# FSWSJE2IZ6BVKJ2.net
KiCad netlist of a schematic drawn in EAGLE
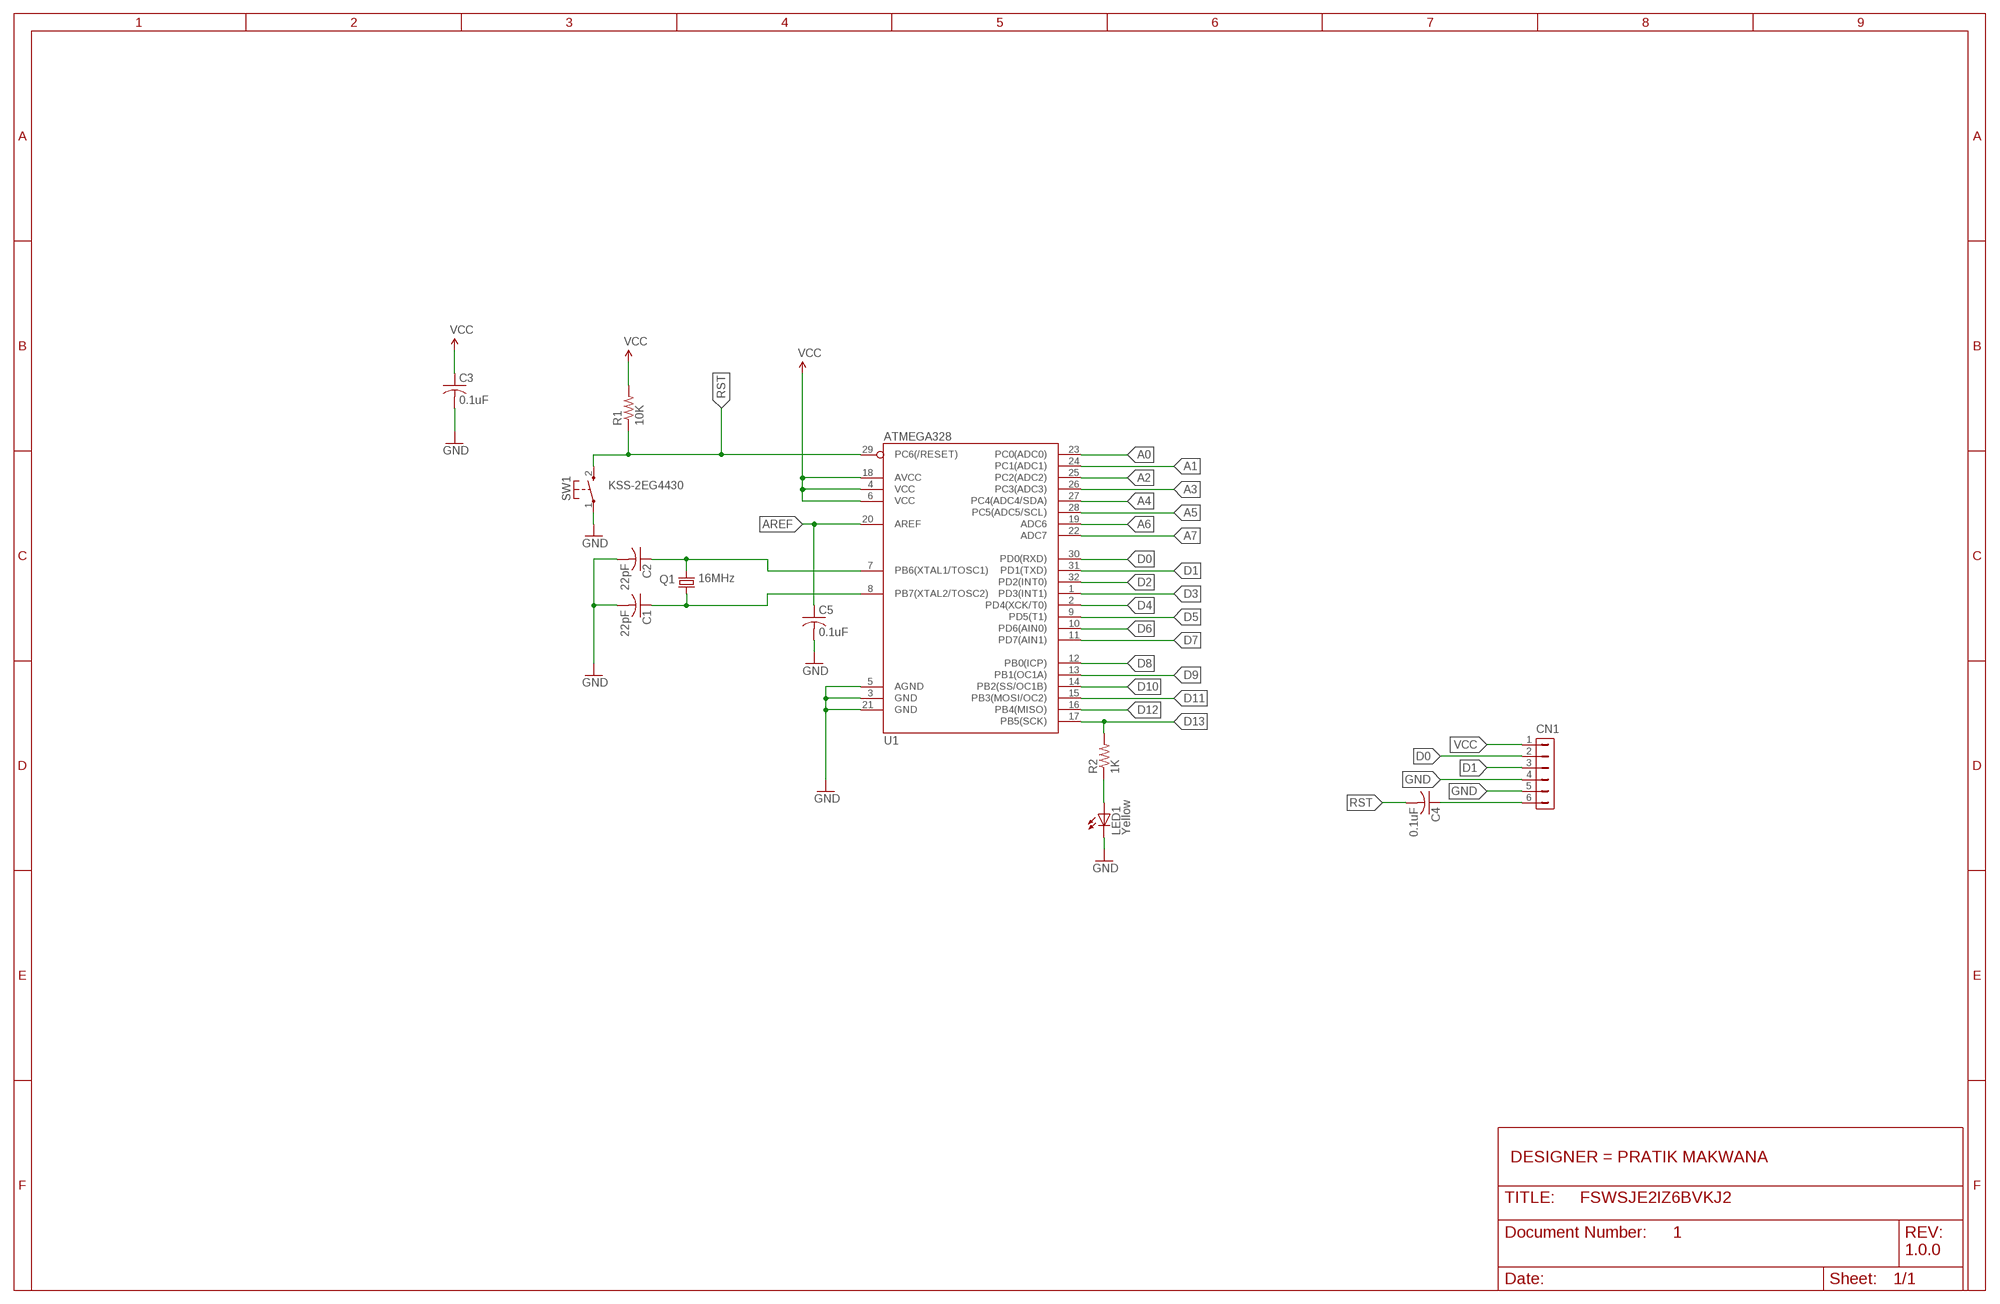
[diagram p0: schematic, sheet 1]

(export (version "E")
  (design (tool "Eeschema 10.0.6"))
  (components
    (comp (ref "C1")
      (value "22pF")
      (footprint "eagle-import:C1206")
      (libsource (lib "eagle-import") (part "C-USC1206"))
    )
    (comp (ref "C2")
      (value "22pF")
      (footprint "eagle-import:C1206")
      (libsource (lib "eagle-import") (part "C-USC1206"))
    )
    (comp (ref "C3")
      (value "0.1uF")
      (footprint "eagle-import:C0805")
      (libsource (lib "eagle-import") (part "C-USC0805"))
    )
    (comp (ref "C4")
      (value "0.1uF")
      (footprint "eagle-import:C0805")
      (libsource (lib "eagle-import") (part "C-USC0805"))
    )
    (comp (ref "C5")
      (value "0.1uF")
      (footprint "eagle-import:C0805")
      (libsource (lib "eagle-import") (part "C-USC0805"))
    )
    (comp (ref "CN1")
      (value "HDR-1X6-SIP-100")
      (footprint "eagle-import:SIP-100-6V")
      (libsource (lib "eagle-import") (part "HDR-1X6-SIP-100"))
    )
    (comp (ref "LED1")
      (value "Yellow")
      (footprint "eagle-import:CHIP-LED0805")
      (libsource (lib "eagle-import") (part "LEDCHIP-LED0805"))
    )
    (comp (ref "Q1")
      (value "16MHz")
      (footprint "eagle-import:HC49_S")
      (libsource (lib "eagle-import") (part "CRYTALHC49S"))
    )
    (comp (ref "R1")
      (value "10K")
      (footprint "eagle-import:R1206")
      (libsource (lib "eagle-import") (part "R-US_R1206"))
    )
    (comp (ref "R2")
      (value "1K")
      (footprint "eagle-import:R1206")
      (libsource (lib "eagle-import") (part "R-US_R1206"))
    )
    (comp (ref "SW1")
      (value "KSS-2EG4430")
      (footprint "eagle-import:KSS-2EG4430")
      (libsource (lib "eagle-import") (part "KSS-2EG4430"))
    )
    (comp (ref "U1")
      (value "ATMEGA328")
      (footprint "eagle-import:TQFP32-08")
      (libsource (lib "eagle-import") (part "ATMEGA328"))
    )
  )
  (nets
    (net (code "1") (name "A0") (class "Default")
      (node (ref "U1") (pin "23") (pinfunction "PC0(ADC0)_23") (pintype "bidirectional"))
    )
    (net (code "2") (name "A1") (class "Default")
      (node (ref "U1") (pin "24") (pinfunction "PC1(ADC1)_24") (pintype "bidirectional"))
    )
    (net (code "3") (name "A2") (class "Default")
      (node (ref "U1") (pin "25") (pinfunction "PC2(ADC2)_25") (pintype "bidirectional"))
    )
    (net (code "4") (name "A3") (class "Default")
      (node (ref "U1") (pin "26") (pinfunction "PC3(ADC3)_26") (pintype "bidirectional"))
    )
    (net (code "5") (name "A4") (class "Default")
      (node (ref "U1") (pin "27") (pinfunction "PC4(ADC4/SDA)_27") (pintype "bidirectional"))
    )
    (net (code "6") (name "A5") (class "Default")
      (node (ref "U1") (pin "28") (pinfunction "PC5(ADC5/SCL)_28") (pintype "bidirectional"))
    )
    (net (code "7") (name "A6") (class "Default")
      (node (ref "U1") (pin "19") (pinfunction "ADC6_19") (pintype "bidirectional"))
    )
    (net (code "8") (name "A7") (class "Default")
      (node (ref "U1") (pin "22") (pinfunction "ADC7_22") (pintype "bidirectional"))
    )
    (net (code "9") (name "AREF") (class "Default")
      (node (ref "C5") (pin "1") (pinfunction "1_1") (pintype "passive"))
      (node (ref "U1") (pin "20") (pinfunction "AREF_20") (pintype "bidirectional"))
    )
    (net (code "10") (name "D0") (class "Default")
      (node (ref "CN1") (pin "2") (pinfunction "2_2") (pintype "passive"))
      (node (ref "U1") (pin "30") (pinfunction "PD0(RXD)_30") (pintype "bidirectional"))
    )
    (net (code "11") (name "D1") (class "Default")
      (node (ref "CN1") (pin "3") (pinfunction "3_3") (pintype "passive"))
      (node (ref "U1") (pin "31") (pinfunction "PD1(TXD)_31") (pintype "bidirectional"))
    )
    (net (code "12") (name "D2") (class "Default")
      (node (ref "U1") (pin "32") (pinfunction "PD2(INT0)_32") (pintype "bidirectional"))
    )
    (net (code "13") (name "D3") (class "Default")
      (node (ref "U1") (pin "1") (pinfunction "PD3(INT1)_1") (pintype "bidirectional"))
    )
    (net (code "14") (name "D4") (class "Default")
      (node (ref "U1") (pin "2") (pinfunction "PD4(XCK/T0)_2") (pintype "bidirectional"))
    )
    (net (code "15") (name "D5") (class "Default")
      (node (ref "U1") (pin "9") (pinfunction "PD5(T1)_9") (pintype "bidirectional"))
    )
    (net (code "16") (name "D6") (class "Default")
      (node (ref "U1") (pin "10") (pinfunction "PD6(AIN0)_10") (pintype "bidirectional"))
    )
    (net (code "17") (name "D7") (class "Default")
      (node (ref "U1") (pin "11") (pinfunction "PD7(AIN1)_11") (pintype "bidirectional"))
    )
    (net (code "18") (name "D8") (class "Default")
      (node (ref "U1") (pin "12") (pinfunction "PB0(ICP)_12") (pintype "bidirectional"))
    )
    (net (code "19") (name "D9") (class "Default")
      (node (ref "U1") (pin "13") (pinfunction "PB1(OC1A)_13") (pintype "bidirectional"))
    )
    (net (code "20") (name "D10") (class "Default")
      (node (ref "U1") (pin "14") (pinfunction "PB2(SS/OC1B)_14") (pintype "bidirectional"))
    )
    (net (code "21") (name "D11") (class "Default")
      (node (ref "U1") (pin "15") (pinfunction "PB3(MOSI/OC2)_15") (pintype "bidirectional"))
    )
    (net (code "22") (name "D12") (class "Default")
      (node (ref "U1") (pin "16") (pinfunction "PB4(MISO)_16") (pintype "bidirectional"))
    )
    (net (code "23") (name "D13") (class "Default")
      (node (ref "R2") (pin "2") (pinfunction "2_2") (pintype "passive"))
      (node (ref "U1") (pin "17") (pinfunction "PB5(SCK)_17") (pintype "bidirectional"))
    )
    (net (code "24") (name "GND") (class "Default")
      (node (ref "C1") (pin "2") (pinfunction "2_2") (pintype "passive"))
      (node (ref "C2") (pin "2") (pinfunction "2_2") (pintype "passive"))
      (node (ref "C3") (pin "2") (pinfunction "2_2") (pintype "passive"))
      (node (ref "C5") (pin "2") (pinfunction "2_2") (pintype "passive"))
      (node (ref "CN1") (pin "4") (pinfunction "4_4") (pintype "passive"))
      (node (ref "CN1") (pin "5") (pinfunction "5_5") (pintype "passive"))
      (node (ref "LED1") (pin "C") (pinfunction "C_C") (pintype "passive"))
      (node (ref "SW1") (pin "1") (pinfunction "P_1") (pintype "passive"))
      (node (ref "U1") (pin "21") (pinfunction "GND_21") (pintype "bidirectional"))
      (node (ref "U1") (pin "3") (pinfunction "GND_3") (pintype "bidirectional"))
      (node (ref "U1") (pin "5") (pinfunction "AGND_5") (pintype "bidirectional"))
    )
    (net (code "25") (name "Net-(C4-Pad1)") (class "Default")
      (node (ref "C4") (pin "1") (pinfunction "1_1") (pintype "passive"))
      (node (ref "CN1") (pin "6") (pinfunction "6_6") (pintype "passive"))
    )
    (net (code "26") (name "Net-(LED1-PadA)") (class "Default")
      (node (ref "LED1") (pin "A") (pinfunction "A_A") (pintype "passive"))
      (node (ref "R2") (pin "1") (pinfunction "1_1") (pintype "passive"))
    )
    (net (code "27") (name "Net-(U1-PB6(XTAL1{slash}TOSC1))") (class "Default")
      (node (ref "C2") (pin "1") (pinfunction "1_1") (pintype "passive"))
      (node (ref "Q1") (pin "2") (pinfunction "2_2") (pintype "passive"))
      (node (ref "U1") (pin "7") (pinfunction "PB6(XTAL1/TOSC1)_7") (pintype "bidirectional"))
    )
    (net (code "28") (name "Net-(U1-PB7(XTAL2{slash}TOSC2))") (class "Default")
      (node (ref "C1") (pin "1") (pinfunction "1_1") (pintype "passive"))
      (node (ref "Q1") (pin "1") (pinfunction "1_1") (pintype "passive"))
      (node (ref "U1") (pin "8") (pinfunction "PB7(XTAL2/TOSC2)_8") (pintype "bidirectional"))
    )
    (net (code "29") (name "RST") (class "Default")
      (node (ref "C4") (pin "2") (pinfunction "2_2") (pintype "passive"))
      (node (ref "R1") (pin "1") (pinfunction "1_1") (pintype "passive"))
      (node (ref "SW1") (pin "2") (pinfunction "S_2") (pintype "passive"))
      (node (ref "U1") (pin "29") (pinfunction "PC6(/RESET)_29") (pintype "bidirectional"))
    )
    (net (code "30") (name "VCC") (class "Default")
      (node (ref "C3") (pin "1") (pinfunction "1_1") (pintype "passive"))
      (node (ref "CN1") (pin "1") (pinfunction "1_1") (pintype "passive"))
      (node (ref "R1") (pin "2") (pinfunction "2_2") (pintype "passive"))
      (node (ref "U1") (pin "18") (pinfunction "AVCC_18") (pintype "bidirectional"))
      (node (ref "U1") (pin "4") (pinfunction "VCC_4") (pintype "bidirectional"))
      (node (ref "U1") (pin "6") (pinfunction "VCC_6") (pintype "bidirectional"))
    )
  )
)
